# 6_pin_connector.net
KiCad netlist of a schematic drawn in Altium Designer
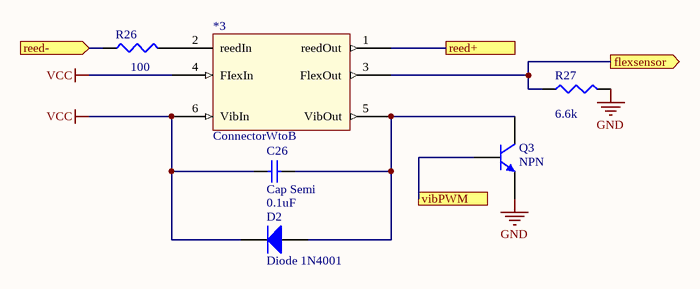
[diagram p0: 6 pin connector.SchDoc]

(export (version "E")
  (design (tool "Eeschema 10.0.6"))
  (components
    (comp (ref "*3")
      (value "ConnectorWtoB")
      (footprint "Connector_wire_to_PCB")
      (libsource (lib "HGCDLibrary") (part "ConnectorWtoB"))
    )
    (comp (ref "C26")
      (value "Cap Semi")
      (footprint "C1206")
      (description "Capacitor (Semiconductor SIM Model)")
      (fields (field (name "ALTIUM_VALUE") "0.1uF") (field (name "PUBLISHER") "Altium Limited"))
      (libsource (lib "Miscellaneous Devices") (part "Cap Semi"))
    )
    (comp (ref "D2")
      (value "Diode 1N4001")
      (footprint "DO-41")
      (description "1 Amp General Purpose Rectifier")
      (fields (field (name "PUBLISHER") "Altium Limited"))
      (libsource (lib "Miscellaneous Devices") (part "Diode 1N4001"))
    )
    (comp (ref "Q3")
      (value "NPN")
      (footprint "TO-226-AA")
      (description "NPN Bipolar Transistor")
      (fields (field (name "PUBLISHER") "Altium Limited"))
      (libsource (lib "Miscellaneous Devices") (part "NPN"))
    )
    (comp (ref "R26")
      (value "100")
      (footprint "J1-0603")
      (description "Resistor")
      (fields (field (name "PUBLISHER") "Altium Limited"))
      (libsource (lib "Miscellaneous Devices") (part "Res3"))
    )
    (comp (ref "R27")
      (value "6.6k")
      (footprint "J1-0603")
      (description "Resistor")
      (fields (field (name "Comment") "Res3") (field (name "PUBLISHER") "Altium Limited"))
      (libsource (lib "Miscellaneous Devices") (part "Res3"))
    )
  )
  (nets
    (net (code "1") (name "/flexsensor") (class "Default")
      (node (ref "*3") (pin "3") (pinfunction "FlexOut_3") (pintype "output"))
      (node (ref "R27") (pin "1") (pinfunction "1_1") (pintype "passive"))
    )
    (net (code "2") (name "/reed+") (class "Default")
      (node (ref "*3") (pin "1") (pinfunction "reedOut_1") (pintype "output"))
    )
    (net (code "3") (name "/reed-") (class "Default")
      (node (ref "R26") (pin "1") (pinfunction "1_1") (pintype "passive"))
    )
    (net (code "4") (name "/vibPWM") (class "Default")
      (node (ref "Q3") (pin "2") (pinfunction "B_2") (pintype "passive"))
    )
    (net (code "5") (name "GND") (class "Default")
      (node (ref "Q3") (pin "3") (pinfunction "E_3") (pintype "passive"))
      (node (ref "R27") (pin "2") (pinfunction "2_2") (pintype "passive"))
    )
    (net (code "6") (name "Net-(*3-VibOut)") (class "Default")
      (node (ref "*3") (pin "5") (pinfunction "VibOut_5") (pintype "output"))
      (node (ref "C26") (pin "2") (pinfunction "2_2") (pintype "passive"))
      (node (ref "D2") (pin "1") (pinfunction "A_1") (pintype "passive"))
      (node (ref "Q3") (pin "1") (pinfunction "C_1") (pintype "passive"))
    )
    (net (code "7") (name "Net-(*3-reedIn)") (class "Default")
      (node (ref "*3") (pin "2") (pinfunction "reedIn_2") (pintype "open_collector"))
      (node (ref "R26") (pin "2") (pinfunction "2_2") (pintype "passive"))
    )
    (net (code "8") (name "VCC") (class "Default")
      (node (ref "*3") (pin "4") (pinfunction "FIexIn_4") (pintype "input"))
      (node (ref "*3") (pin "6") (pinfunction "VibIn_6") (pintype "input"))
      (node (ref "C26") (pin "1") (pinfunction "1_1") (pintype "passive"))
      (node (ref "D2") (pin "2") (pinfunction "K_2") (pintype "passive"))
    )
  )
)
